# V1_0.net
KiCad netlist of a schematic drawn in Altium Designer
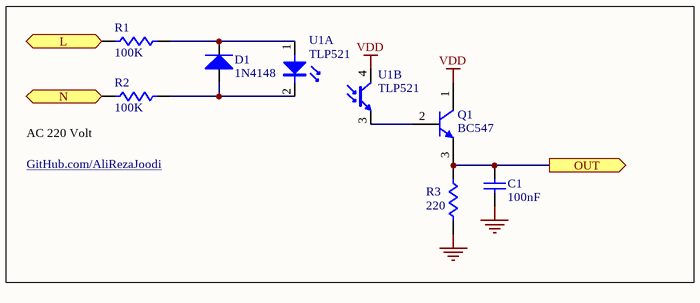
[diagram p0: V1.0.SchDoc]

(export (version "E")
  (design (tool "Eeschema 10.0.6"))
  (components
    (comp (ref "C1")
      (value "100nF")
      (footprint "CAPNTO5.08-7.37x3.94")
      (description "Capacitor")
      (fields (field (name "MANUFACTURER") "Generic Components") (field (name "PUBLISHER") "Altium Limited"))
      (libsource (lib "Miscellaneous Devices") (part "Cap"))
    )
    (comp (ref "D1")
      (value "1N4148")
      (footprint "DIODE0.2_")
      (description "Default Diode")
      (fields (field (name "MANUFACTURER") "Generic Components") (field (name "PUBLISHER") "Altium Limited"))
      (libsource (lib "Miscellaneous Devices") (part "Diode"))
    )
    (comp (ref "Q1")
      (value "BC547")
      (footprint "TO92C")
      (description "Silicon Bipolar Transistor")
      (libsource (lib "my Libraries") (part "NPN"))
    )
    (comp (ref "R1")
      (value "100K")
      (footprint "AXIAL-0.4")
      (description "Resistor")
      (fields (field (name "MANUFACTURER") "Generic Components") (field (name "PUBLISHER") "Altium Limited"))
      (libsource (lib "Miscellaneous Devices") (part "Res1"))
    )
    (comp (ref "R2")
      (value "100K")
      (footprint "AXIAL-0.4")
      (description "Resistor")
      (fields (field (name "MANUFACTURER") "Generic Components") (field (name "PUBLISHER") "Altium Limited"))
      (libsource (lib "Miscellaneous Devices") (part "Res1"))
    )
    (comp (ref "R3")
      (value "220")
      (footprint "AXIAL-0.4")
      (description "Resistor")
      (fields (field (name "MANUFACTURER") "Generic Components") (field (name "PUBLISHER") "Altium Limited"))
      (libsource (lib "Miscellaneous Devices") (part "Res1"))
    )
    (comp (ref "U1")
      (value "TLP521")
      (footprint "DIP-4")
      (fields (field (name "PUBLISHER") "Altium Limited"))
      (libsource (lib "my Libraries") (part "Optoisolator"))
    )
  )
  (nets
    (net (code "1") (name "/L") (class "Default")
      (node (ref "R1") (pin "1") (pinfunction "1_1") (pintype "passive"))
    )
    (net (code "2") (name "/N") (class "Default")
      (node (ref "R2") (pin "1") (pinfunction "1_1") (pintype "passive"))
    )
    (net (code "3") (name "/OUT") (class "Default")
      (node (ref "C1") (pin "2") (pinfunction "2_2") (pintype "passive"))
      (node (ref "Q1") (pin "3") (pinfunction "E_3") (pintype "passive"))
      (node (ref "R3") (pin "1") (pinfunction "1_1") (pintype "passive"))
    )
    (net (code "4") (name "GND") (class "Default")
      (node (ref "C1") (pin "1") (pinfunction "1_1") (pintype "passive"))
      (node (ref "R3") (pin "2") (pinfunction "2_2") (pintype "passive"))
    )
    (net (code "5") (name "Net-(D1-A)") (class "Default")
      (node (ref "D1") (pin "1") (pinfunction "A_1") (pintype "passive"))
      (node (ref "R2") (pin "2") (pinfunction "2_2") (pintype "passive"))
      (node (ref "U1") (pin "2") (pinfunction "K_2") (pintype "power_in"))
    )
    (net (code "6") (name "Net-(D1-K)") (class "Default")
      (node (ref "D1") (pin "2") (pinfunction "K_2") (pintype "passive"))
      (node (ref "R1") (pin "2") (pinfunction "2_2") (pintype "passive"))
      (node (ref "U1") (pin "1") (pinfunction "A_1") (pintype "power_in"))
    )
    (net (code "7") (name "Net-(Q1-B)") (class "Default")
      (node (ref "Q1") (pin "2") (pinfunction "B_2") (pintype "passive"))
      (node (ref "U1") (pin "3") (pinfunction "E_3") (pintype "passive"))
    )
    (net (code "8") (name "VDD") (class "Default")
      (node (ref "Q1") (pin "1") (pinfunction "C_1") (pintype "passive"))
      (node (ref "U1") (pin "4") (pinfunction "C_4") (pintype "passive"))
    )
  )
)
